# SAT_GPS_CLOCK_IC.net
KiCad netlist of a schematic drawn in Altium Designer
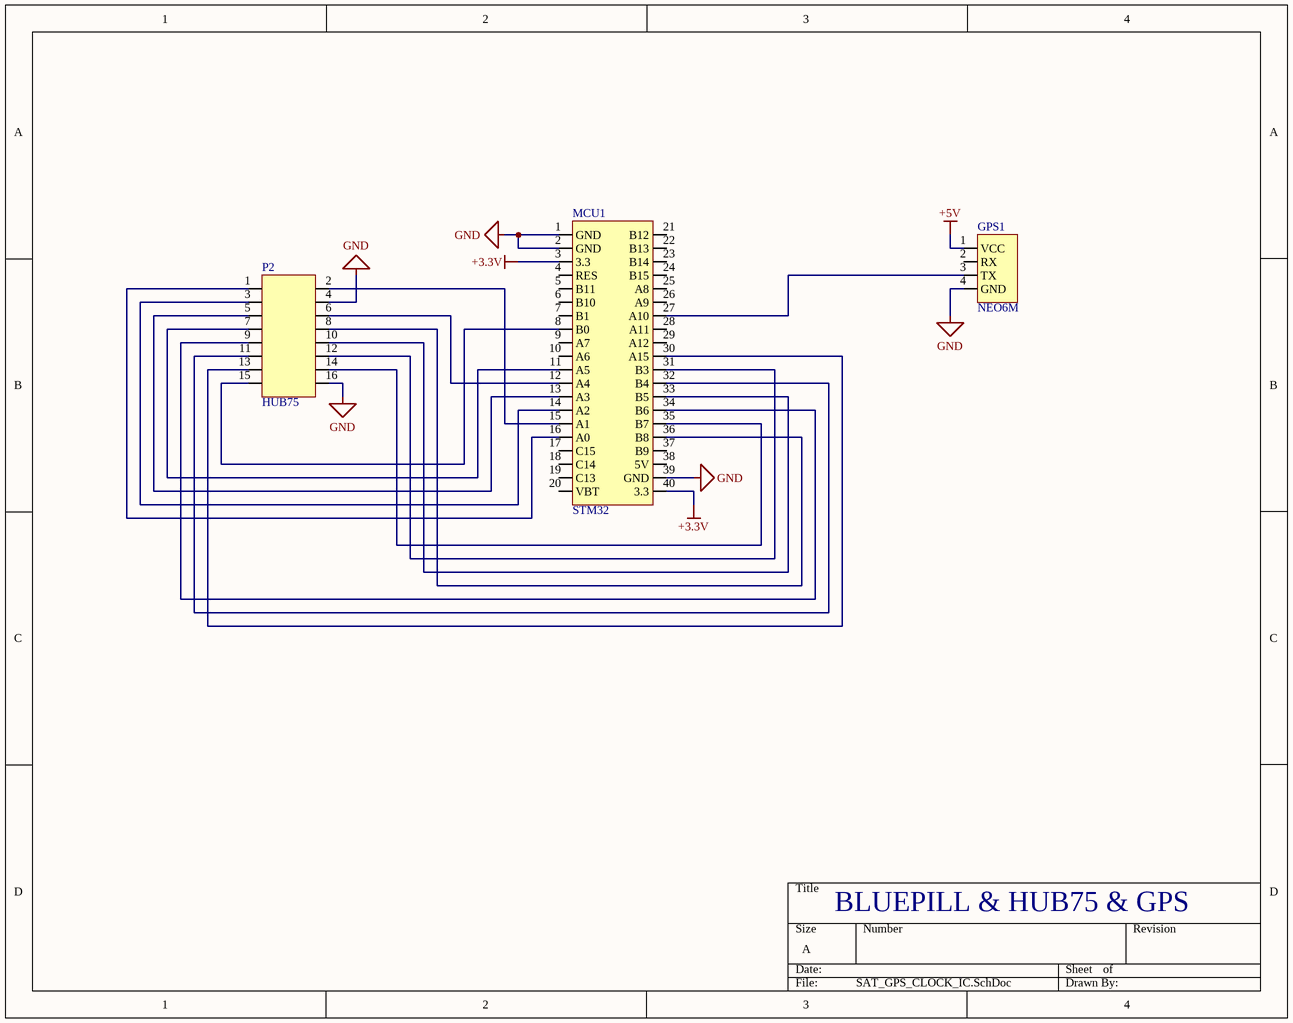
[diagram p0: SAT_GPS_CLOCK_IC.SchDoc]

(export (version "E")
  (design (tool "Eeschema 10.0.6"))
  (components
    (comp (ref "GPS1")
      (value "NEO6M")
      (footprint "THT_NEO6M_FINAL")
      (description "GPS Module NEO6M Breakout Board")
      (libsource (lib "THT_NEO6M_FINAL") (part "THT_NEO6M_FINAL"))
    )
    (comp (ref "MCU1")
      (value "STM32")
      (footprint "STM32F103C6T6_THT")
      (description "STM32F103C8T6 Blue Pill")
      (libsource (lib "STM32F103C6T6_THT") (part "STM32F103C6T6_THT"))
    )
    (comp (ref "P2")
      (value "HUB75")
      (footprint "THT_CON_2316S-16G")
      (description "Connector 2316S-16G 16 Pin 2.54 Pitch")
      (libsource (lib "THT_CON_2316S-16G") (part "THT_CON_2316S-16G"))
    )
  )
  (nets
    (net (code "1") (name "+3.3V") (class "Default")
      (node (ref "MCU1") (pin "3") (pinfunction "3.3_3") (pintype "passive"))
      (node (ref "MCU1") (pin "40") (pinfunction "3.3_40") (pintype "passive"))
    )
    (net (code "2") (name "+5V") (class "Default")
      (node (ref "GPS1") (pin "1") (pinfunction "VCC_1") (pintype "passive"))
    )
    (net (code "3") (name "GND") (class "Default")
      (node (ref "GPS1") (pin "4") (pinfunction "GND_4") (pintype "passive"))
      (node (ref "MCU1") (pin "1") (pinfunction "GND_1") (pintype "passive"))
      (node (ref "MCU1") (pin "2") (pinfunction "GND_2") (pintype "passive"))
      (node (ref "MCU1") (pin "39") (pinfunction "GND_39") (pintype "passive"))
      (node (ref "P2") (pin "16") (pinfunction "16_16") (pintype "passive"))
      (node (ref "P2") (pin "4") (pinfunction "4_4") (pintype "passive"))
    )
    (net (code "4") (name "Net-(GPS1-TX)") (class "Default")
      (node (ref "GPS1") (pin "3") (pinfunction "TX_3") (pintype "passive"))
      (node (ref "MCU1") (pin "27") (pinfunction "A10_27") (pintype "passive"))
    )
    (net (code "5") (name "Net-(MCU1-A0)") (class "Default")
      (node (ref "MCU1") (pin "16") (pinfunction "A0_16") (pintype "passive"))
      (node (ref "P2") (pin "1") (pinfunction "1_1") (pintype "passive"))
    )
    (net (code "6") (name "Net-(MCU1-A1)") (class "Default")
      (node (ref "MCU1") (pin "15") (pinfunction "A1_15") (pintype "passive"))
      (node (ref "P2") (pin "2") (pinfunction "2_2") (pintype "passive"))
    )
    (net (code "7") (name "Net-(MCU1-A2)") (class "Default")
      (node (ref "MCU1") (pin "14") (pinfunction "A2_14") (pintype "passive"))
      (node (ref "P2") (pin "3") (pinfunction "3_3") (pintype "passive"))
    )
    (net (code "8") (name "Net-(MCU1-A3)") (class "Default")
      (node (ref "MCU1") (pin "13") (pinfunction "A3_13") (pintype "passive"))
      (node (ref "P2") (pin "5") (pinfunction "5_5") (pintype "passive"))
    )
    (net (code "9") (name "Net-(MCU1-A4)") (class "Default")
      (node (ref "MCU1") (pin "12") (pinfunction "A4_12") (pintype "passive"))
      (node (ref "P2") (pin "6") (pinfunction "6_6") (pintype "passive"))
    )
    (net (code "10") (name "Net-(MCU1-A5)") (class "Default")
      (node (ref "MCU1") (pin "11") (pinfunction "A5_11") (pintype "passive"))
      (node (ref "P2") (pin "7") (pinfunction "7_7") (pintype "passive"))
    )
    (net (code "11") (name "Net-(MCU1-A15)") (class "Default")
      (node (ref "MCU1") (pin "30") (pinfunction "A15_30") (pintype "passive"))
      (node (ref "P2") (pin "13") (pinfunction "13_13") (pintype "passive"))
    )
    (net (code "12") (name "Net-(MCU1-B0)") (class "Default")
      (node (ref "MCU1") (pin "8") (pinfunction "B0_8") (pintype "passive"))
      (node (ref "P2") (pin "15") (pinfunction "15_15") (pintype "passive"))
    )
    (net (code "13") (name "Net-(MCU1-B3)") (class "Default")
      (node (ref "MCU1") (pin "31") (pinfunction "B3_31") (pintype "passive"))
      (node (ref "P2") (pin "12") (pinfunction "12_12") (pintype "passive"))
    )
    (net (code "14") (name "Net-(MCU1-B4)") (class "Default")
      (node (ref "MCU1") (pin "32") (pinfunction "B4_32") (pintype "passive"))
      (node (ref "P2") (pin "11") (pinfunction "11_11") (pintype "passive"))
    )
    (net (code "15") (name "Net-(MCU1-B5)") (class "Default")
      (node (ref "MCU1") (pin "33") (pinfunction "B5_33") (pintype "passive"))
      (node (ref "P2") (pin "10") (pinfunction "10_10") (pintype "passive"))
    )
    (net (code "16") (name "Net-(MCU1-B6)") (class "Default")
      (node (ref "MCU1") (pin "34") (pinfunction "B6_34") (pintype "passive"))
      (node (ref "P2") (pin "9") (pinfunction "9_9") (pintype "passive"))
    )
    (net (code "17") (name "Net-(MCU1-B7)") (class "Default")
      (node (ref "MCU1") (pin "35") (pinfunction "B7_35") (pintype "passive"))
      (node (ref "P2") (pin "14") (pinfunction "14_14") (pintype "passive"))
    )
    (net (code "18") (name "Net-(MCU1-B8)") (class "Default")
      (node (ref "MCU1") (pin "36") (pinfunction "B8_36") (pintype "passive"))
      (node (ref "P2") (pin "8") (pinfunction "8_8") (pintype "passive"))
    )
    (net (code "19") (name "unconnected-(GPS1-RX-Pad2)") (class "Default")
      (node (ref "GPS1") (pin "2") (pinfunction "RX_2") (pintype "passive"))
    )
    (net (code "20") (name "unconnected-(MCU1-5V-Pad38)") (class "Default")
      (node (ref "MCU1") (pin "38") (pinfunction "5V_38") (pintype "passive"))
    )
    (net (code "21") (name "unconnected-(MCU1-A6-Pad10)") (class "Default")
      (node (ref "MCU1") (pin "10") (pinfunction "A6_10") (pintype "passive"))
    )
    (net (code "22") (name "unconnected-(MCU1-A7-Pad9)") (class "Default")
      (node (ref "MCU1") (pin "9") (pinfunction "A7_9") (pintype "passive"))
    )
    (net (code "23") (name "unconnected-(MCU1-A8-Pad25)") (class "Default")
      (node (ref "MCU1") (pin "25") (pinfunction "A8_25") (pintype "passive"))
    )
    (net (code "24") (name "unconnected-(MCU1-A9-Pad26)") (class "Default")
      (node (ref "MCU1") (pin "26") (pinfunction "A9_26") (pintype "passive"))
    )
    (net (code "25") (name "unconnected-(MCU1-A11-Pad28)") (class "Default")
      (node (ref "MCU1") (pin "28") (pinfunction "A11_28") (pintype "passive"))
    )
    (net (code "26") (name "unconnected-(MCU1-A12-Pad29)") (class "Default")
      (node (ref "MCU1") (pin "29") (pinfunction "A12_29") (pintype "passive"))
    )
    (net (code "27") (name "unconnected-(MCU1-B1-Pad7)") (class "Default")
      (node (ref "MCU1") (pin "7") (pinfunction "B1_7") (pintype "passive"))
    )
    (net (code "28") (name "unconnected-(MCU1-B9-Pad37)") (class "Default")
      (node (ref "MCU1") (pin "37") (pinfunction "B9_37") (pintype "passive"))
    )
    (net (code "29") (name "unconnected-(MCU1-B10-Pad6)") (class "Default")
      (node (ref "MCU1") (pin "6") (pinfunction "B10_6") (pintype "passive"))
    )
    (net (code "30") (name "unconnected-(MCU1-B11-Pad5)") (class "Default")
      (node (ref "MCU1") (pin "5") (pinfunction "B11_5") (pintype "passive"))
    )
    (net (code "31") (name "unconnected-(MCU1-B12-Pad21)") (class "Default")
      (node (ref "MCU1") (pin "21") (pinfunction "B12_21") (pintype "passive"))
    )
    (net (code "32") (name "unconnected-(MCU1-B13-Pad22)") (class "Default")
      (node (ref "MCU1") (pin "22") (pinfunction "B13_22") (pintype "passive"))
    )
    (net (code "33") (name "unconnected-(MCU1-B14-Pad23)") (class "Default")
      (node (ref "MCU1") (pin "23") (pinfunction "B14_23") (pintype "passive"))
    )
    (net (code "34") (name "unconnected-(MCU1-B15-Pad24)") (class "Default")
      (node (ref "MCU1") (pin "24") (pinfunction "B15_24") (pintype "passive"))
    )
    (net (code "35") (name "unconnected-(MCU1-C13-Pad19)") (class "Default")
      (node (ref "MCU1") (pin "19") (pinfunction "C13_19") (pintype "passive"))
    )
    (net (code "36") (name "unconnected-(MCU1-C14-Pad18)") (class "Default")
      (node (ref "MCU1") (pin "18") (pinfunction "C14_18") (pintype "passive"))
    )
    (net (code "37") (name "unconnected-(MCU1-C15-Pad17)") (class "Default")
      (node (ref "MCU1") (pin "17") (pinfunction "C15_17") (pintype "passive"))
    )
    (net (code "38") (name "unconnected-(MCU1-RES-Pad4)") (class "Default")
      (node (ref "MCU1") (pin "4") (pinfunction "RES_4") (pintype "passive"))
    )
    (net (code "39") (name "unconnected-(MCU1-VBT-Pad20)") (class "Default")
      (node (ref "MCU1") (pin "20") (pinfunction "VBT_20") (pintype "passive"))
    )
  )
)
